# A.net
KiCad netlist of a schematic drawn in EAGLE
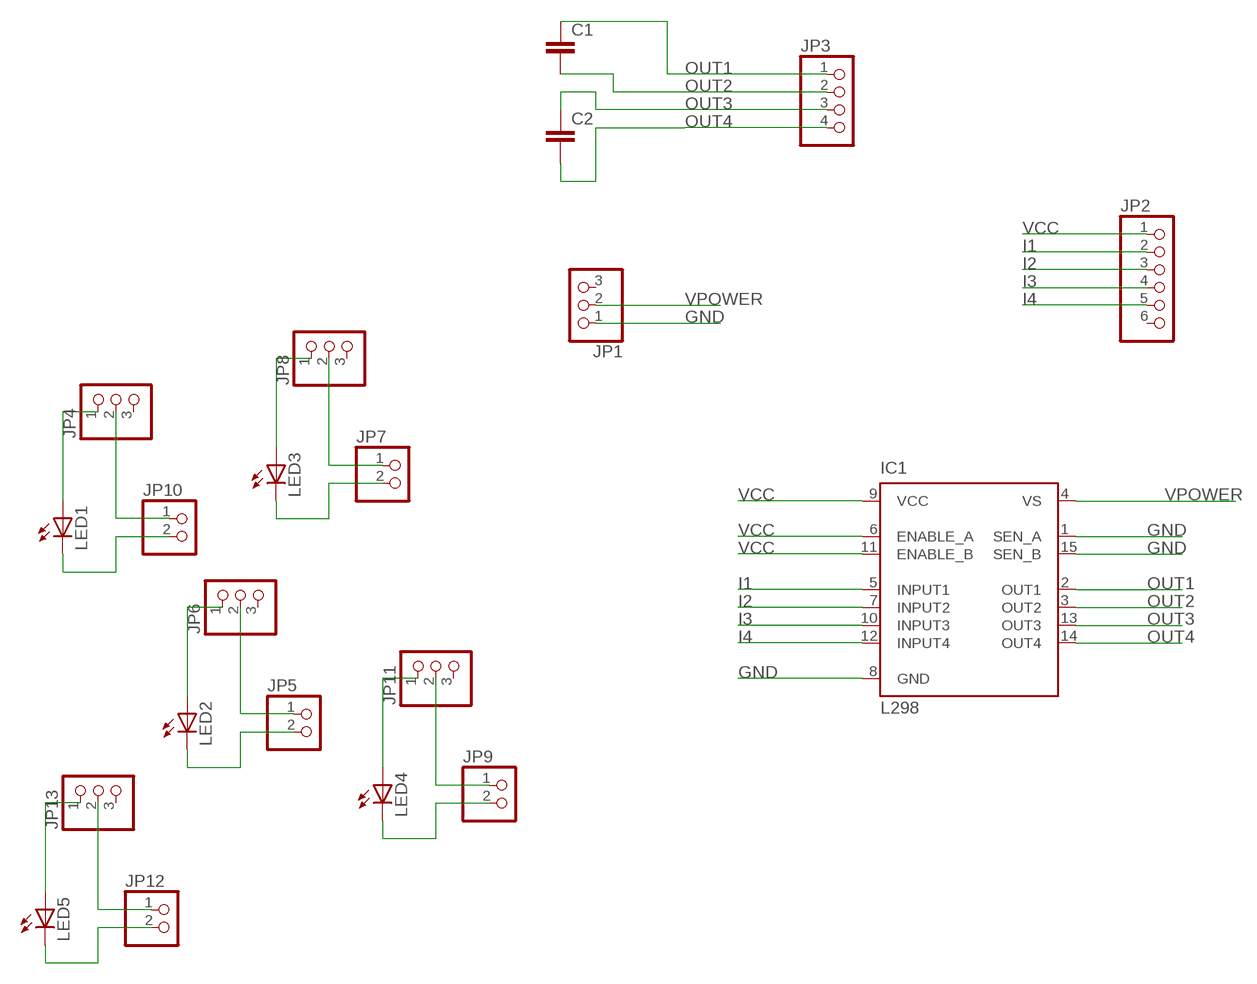
[diagram p0: schematic, sheet 1]

(export (version "E")
  (design (tool "Eeschema 10.0.6"))
  (components
    (comp (ref "C1")
      (value "C2,5-3")
      (footprint "eagle-import:C2.5-3")
      (libsource (lib "eagle-import") (part "C2,5-3"))
    )
    (comp (ref "C2")
      (value "C2,5-3")
      (footprint "eagle-import:C2.5-3")
      (libsource (lib "eagle-import") (part "C2,5-3"))
    )
    (comp (ref "IC1")
      (value "L298")
      (footprint "eagle-import:MULTIWATT-15")
      (fields (field (name "MPN") "L298N"))
      (libsource (lib "eagle-import") (part "L298"))
    )
    (comp (ref "JP1")
      (value "PINHD-1X3")
      (footprint "eagle-import:1X03")
      (libsource (lib "eagle-import") (part "PINHD-1X3"))
    )
    (comp (ref "JP2")
      (value "PINHD-1X6")
      (footprint "eagle-import:1X06")
      (libsource (lib "eagle-import") (part "PINHD-1X6"))
    )
    (comp (ref "JP3")
      (value "PINHD-1X4")
      (footprint "eagle-import:1X04")
      (libsource (lib "eagle-import") (part "PINHD-1X4"))
    )
    (comp (ref "JP4")
      (value "PINHD-1X3")
      (footprint "eagle-import:1X03")
      (libsource (lib "eagle-import") (part "PINHD-1X3"))
    )
    (comp (ref "JP5")
      (value "PINHD-1X2")
      (footprint "eagle-import:1X02")
      (libsource (lib "eagle-import") (part "PINHD-1X2"))
    )
    (comp (ref "JP6")
      (value "PINHD-1X3")
      (footprint "eagle-import:1X03")
      (libsource (lib "eagle-import") (part "PINHD-1X3"))
    )
    (comp (ref "JP7")
      (value "PINHD-1X2")
      (footprint "eagle-import:1X02")
      (libsource (lib "eagle-import") (part "PINHD-1X2"))
    )
    (comp (ref "JP8")
      (value "PINHD-1X3")
      (footprint "eagle-import:1X03")
      (libsource (lib "eagle-import") (part "PINHD-1X3"))
    )
    (comp (ref "JP9")
      (value "PINHD-1X2")
      (footprint "eagle-import:1X02")
      (libsource (lib "eagle-import") (part "PINHD-1X2"))
    )
    (comp (ref "JP10")
      (value "PINHD-1X2")
      (footprint "eagle-import:1X02")
      (libsource (lib "eagle-import") (part "PINHD-1X2"))
    )
    (comp (ref "JP11")
      (value "PINHD-1X3")
      (footprint "eagle-import:1X03")
      (libsource (lib "eagle-import") (part "PINHD-1X3"))
    )
    (comp (ref "JP12")
      (value "PINHD-1X2")
      (footprint "eagle-import:1X02")
      (libsource (lib "eagle-import") (part "PINHD-1X2"))
    )
    (comp (ref "JP13")
      (value "PINHD-1X3")
      (footprint "eagle-import:1X03")
      (libsource (lib "eagle-import") (part "PINHD-1X3"))
    )
    (comp (ref "LED1")
      (value "LED5MM")
      (footprint "eagle-import:LED5MM")
      (libsource (lib "eagle-import") (part "LED5MM"))
    )
    (comp (ref "LED2")
      (value "LED5MM")
      (footprint "eagle-import:LED5MM")
      (libsource (lib "eagle-import") (part "LED5MM"))
    )
    (comp (ref "LED3")
      (value "LED5MM")
      (footprint "eagle-import:LED5MM")
      (libsource (lib "eagle-import") (part "LED5MM"))
    )
    (comp (ref "LED4")
      (value "LED5MM")
      (footprint "eagle-import:LED5MM")
      (libsource (lib "eagle-import") (part "LED5MM"))
    )
    (comp (ref "LED5")
      (value "LED5MM")
      (footprint "eagle-import:LED5MM")
      (libsource (lib "eagle-import") (part "LED5MM"))
    )
  )
  (nets
    (net (code "1") (name "/GND") (class "Default")
      (node (ref "IC1") (pin "1") (pinfunction "SEN_A_1") (pintype "input"))
      (node (ref "IC1") (pin "15") (pinfunction "SEN_B_15") (pintype "input"))
      (node (ref "IC1") (pin "8") (pinfunction "GND_8") (pintype "power_in"))
      (node (ref "JP1") (pin "1") (pinfunction "1_1") (pintype "passive"))
    )
    (net (code "2") (name "/I1") (class "Default")
      (node (ref "IC1") (pin "5") (pinfunction "INPUT1_5") (pintype "input"))
      (node (ref "JP2") (pin "2") (pinfunction "2_2") (pintype "passive"))
    )
    (net (code "3") (name "/I2") (class "Default")
      (node (ref "IC1") (pin "7") (pinfunction "INPUT2_7") (pintype "input"))
      (node (ref "JP2") (pin "3") (pinfunction "3_3") (pintype "passive"))
    )
    (net (code "4") (name "/I3") (class "Default")
      (node (ref "IC1") (pin "10") (pinfunction "INPUT3_10") (pintype "input"))
      (node (ref "JP2") (pin "4") (pinfunction "4_4") (pintype "passive"))
    )
    (net (code "5") (name "/I4") (class "Default")
      (node (ref "IC1") (pin "12") (pinfunction "INPUT4_12") (pintype "input"))
      (node (ref "JP2") (pin "5") (pinfunction "5_5") (pintype "passive"))
    )
    (net (code "6") (name "/OUT1") (class "Default")
      (node (ref "C1") (pin "1") (pinfunction "1_1") (pintype "passive"))
      (node (ref "IC1") (pin "2") (pinfunction "OUT1_2") (pintype "output"))
      (node (ref "JP3") (pin "1") (pinfunction "1_1") (pintype "passive"))
    )
    (net (code "7") (name "/OUT2") (class "Default")
      (node (ref "C1") (pin "2") (pinfunction "2_2") (pintype "passive"))
      (node (ref "IC1") (pin "3") (pinfunction "OUT2_3") (pintype "output"))
      (node (ref "JP3") (pin "2") (pinfunction "2_2") (pintype "passive"))
    )
    (net (code "8") (name "/OUT3") (class "Default")
      (node (ref "C2") (pin "1") (pinfunction "1_1") (pintype "passive"))
      (node (ref "IC1") (pin "13") (pinfunction "OUT3_13") (pintype "output"))
      (node (ref "JP3") (pin "3") (pinfunction "3_3") (pintype "passive"))
    )
    (net (code "9") (name "/OUT4") (class "Default")
      (node (ref "C2") (pin "2") (pinfunction "2_2") (pintype "passive"))
      (node (ref "IC1") (pin "14") (pinfunction "OUT4_14") (pintype "output"))
      (node (ref "JP3") (pin "4") (pinfunction "4_4") (pintype "passive"))
    )
    (net (code "10") (name "/VCC") (class "Default")
      (node (ref "IC1") (pin "11") (pinfunction "ENABLE_B_11") (pintype "input"))
      (node (ref "IC1") (pin "6") (pinfunction "ENABLE_A_6") (pintype "input"))
      (node (ref "IC1") (pin "9") (pinfunction "VCC_9") (pintype "power_in"))
      (node (ref "JP2") (pin "1") (pinfunction "1_1") (pintype "passive"))
    )
    (net (code "11") (name "/VPOWER") (class "Default")
      (node (ref "IC1") (pin "4") (pinfunction "VS_4") (pintype "power_in"))
      (node (ref "JP1") (pin "2") (pinfunction "2_2") (pintype "passive"))
    )
    (net (code "12") (name "Net-(JP4-Pad1)") (class "Default")
      (node (ref "JP4") (pin "1") (pinfunction "1_1") (pintype "passive"))
      (node (ref "LED1") (pin "A") (pinfunction "A_A") (pintype "passive"))
    )
    (net (code "13") (name "Net-(JP5-Pad1)") (class "Default")
      (node (ref "JP5") (pin "1") (pinfunction "1_1") (pintype "passive"))
      (node (ref "JP6") (pin "2") (pinfunction "2_2") (pintype "passive"))
    )
    (net (code "14") (name "Net-(JP6-Pad1)") (class "Default")
      (node (ref "JP6") (pin "1") (pinfunction "1_1") (pintype "passive"))
      (node (ref "LED2") (pin "A") (pinfunction "A_A") (pintype "passive"))
    )
    (net (code "15") (name "Net-(JP7-Pad1)") (class "Default")
      (node (ref "JP7") (pin "1") (pinfunction "1_1") (pintype "passive"))
      (node (ref "JP8") (pin "2") (pinfunction "2_2") (pintype "passive"))
    )
    (net (code "16") (name "Net-(JP8-Pad1)") (class "Default")
      (node (ref "JP8") (pin "1") (pinfunction "1_1") (pintype "passive"))
      (node (ref "LED3") (pin "A") (pinfunction "A_A") (pintype "passive"))
    )
    (net (code "17") (name "Net-(JP10-Pad1)") (class "Default")
      (node (ref "JP10") (pin "1") (pinfunction "1_1") (pintype "passive"))
      (node (ref "JP4") (pin "2") (pinfunction "2_2") (pintype "passive"))
    )
    (net (code "18") (name "Net-(JP11-Pad1)") (class "Default")
      (node (ref "JP11") (pin "1") (pinfunction "1_1") (pintype "passive"))
      (node (ref "LED4") (pin "A") (pinfunction "A_A") (pintype "passive"))
    )
    (net (code "19") (name "Net-(JP11-Pad2)") (class "Default")
      (node (ref "JP11") (pin "2") (pinfunction "2_2") (pintype "passive"))
      (node (ref "JP9") (pin "1") (pinfunction "1_1") (pintype "passive"))
    )
    (net (code "20") (name "Net-(JP12-Pad1)") (class "Default")
      (node (ref "JP12") (pin "1") (pinfunction "1_1") (pintype "passive"))
      (node (ref "JP13") (pin "2") (pinfunction "2_2") (pintype "passive"))
    )
    (net (code "21") (name "Net-(JP13-Pad1)") (class "Default")
      (node (ref "JP13") (pin "1") (pinfunction "1_1") (pintype "passive"))
      (node (ref "LED5") (pin "A") (pinfunction "A_A") (pintype "passive"))
    )
    (net (code "22") (name "Net-(LED1-C)") (class "Default")
      (node (ref "JP10") (pin "2") (pinfunction "2_2") (pintype "passive"))
      (node (ref "LED1") (pin "K") (pinfunction "C_K") (pintype "passive"))
    )
    (net (code "23") (name "Net-(LED2-C)") (class "Default")
      (node (ref "JP5") (pin "2") (pinfunction "2_2") (pintype "passive"))
      (node (ref "LED2") (pin "K") (pinfunction "C_K") (pintype "passive"))
    )
    (net (code "24") (name "Net-(LED3-C)") (class "Default")
      (node (ref "JP7") (pin "2") (pinfunction "2_2") (pintype "passive"))
      (node (ref "LED3") (pin "K") (pinfunction "C_K") (pintype "passive"))
    )
    (net (code "25") (name "Net-(LED4-C)") (class "Default")
      (node (ref "JP9") (pin "2") (pinfunction "2_2") (pintype "passive"))
      (node (ref "LED4") (pin "K") (pinfunction "C_K") (pintype "passive"))
    )
    (net (code "26") (name "Net-(LED5-C)") (class "Default")
      (node (ref "JP12") (pin "2") (pinfunction "2_2") (pintype "passive"))
      (node (ref "LED5") (pin "K") (pinfunction "C_K") (pintype "passive"))
    )
    (net (code "27") (name "unconnected-(JP1-Pad3)") (class "Default")
      (node (ref "JP1") (pin "3") (pinfunction "3_3") (pintype "passive"))
    )
    (net (code "28") (name "unconnected-(JP2-Pad6)") (class "Default")
      (node (ref "JP2") (pin "6") (pinfunction "6_6") (pintype "passive"))
    )
    (net (code "29") (name "unconnected-(JP4-Pad3)") (class "Default")
      (node (ref "JP4") (pin "3") (pinfunction "3_3") (pintype "passive"))
    )
    (net (code "30") (name "unconnected-(JP6-Pad3)") (class "Default")
      (node (ref "JP6") (pin "3") (pinfunction "3_3") (pintype "passive"))
    )
    (net (code "31") (name "unconnected-(JP8-Pad3)") (class "Default")
      (node (ref "JP8") (pin "3") (pinfunction "3_3") (pintype "passive"))
    )
    (net (code "32") (name "unconnected-(JP11-Pad3)") (class "Default")
      (node (ref "JP11") (pin "3") (pinfunction "3_3") (pintype "passive"))
    )
    (net (code "33") (name "unconnected-(JP13-Pad3)") (class "Default")
      (node (ref "JP13") (pin "3") (pinfunction "3_3") (pintype "passive"))
    )
  )
)
